# design2.net
KiCad netlist of a schematic drawn in EAGLE
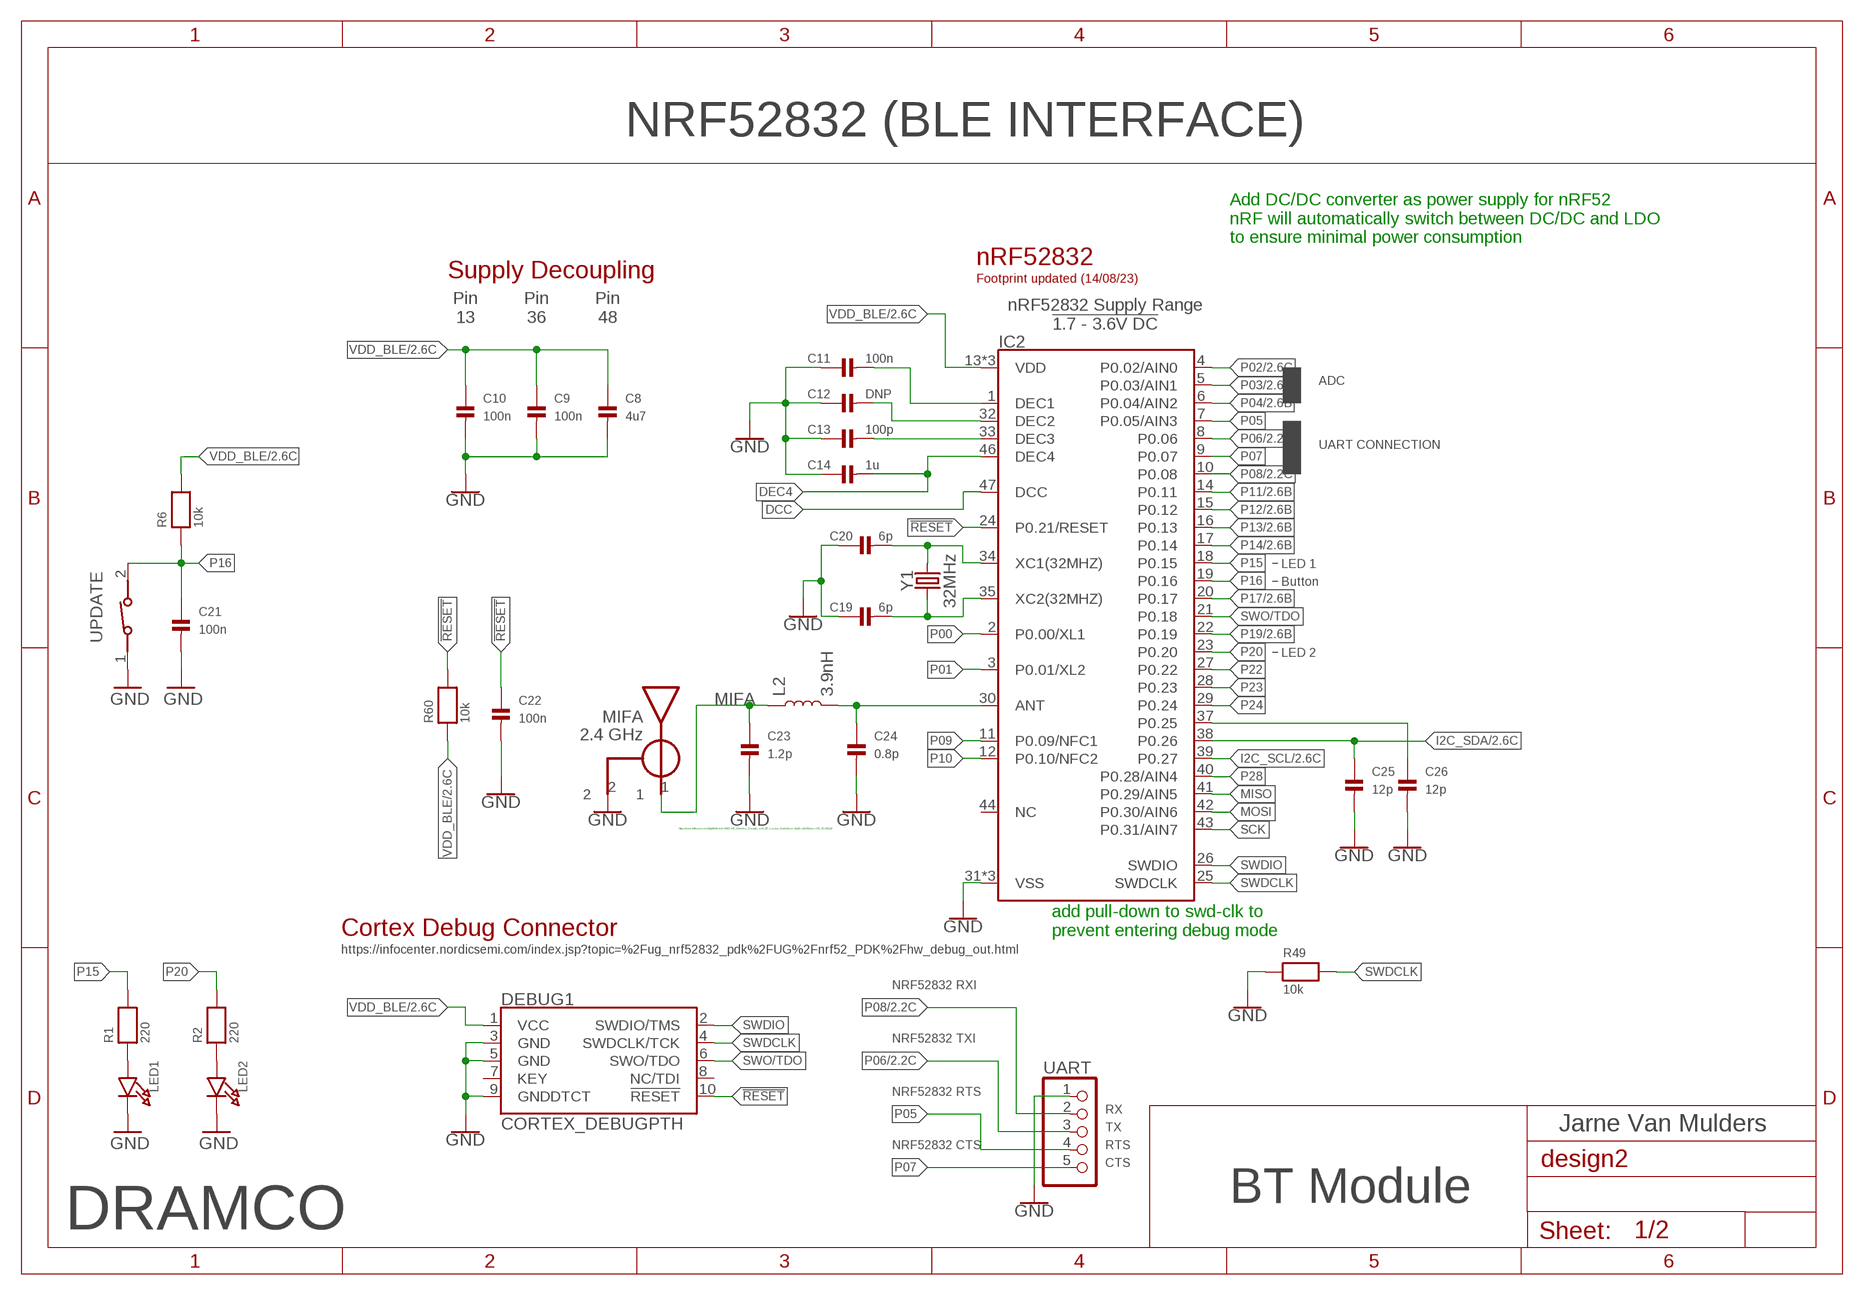
[diagram p0: schematic, sheet 1]
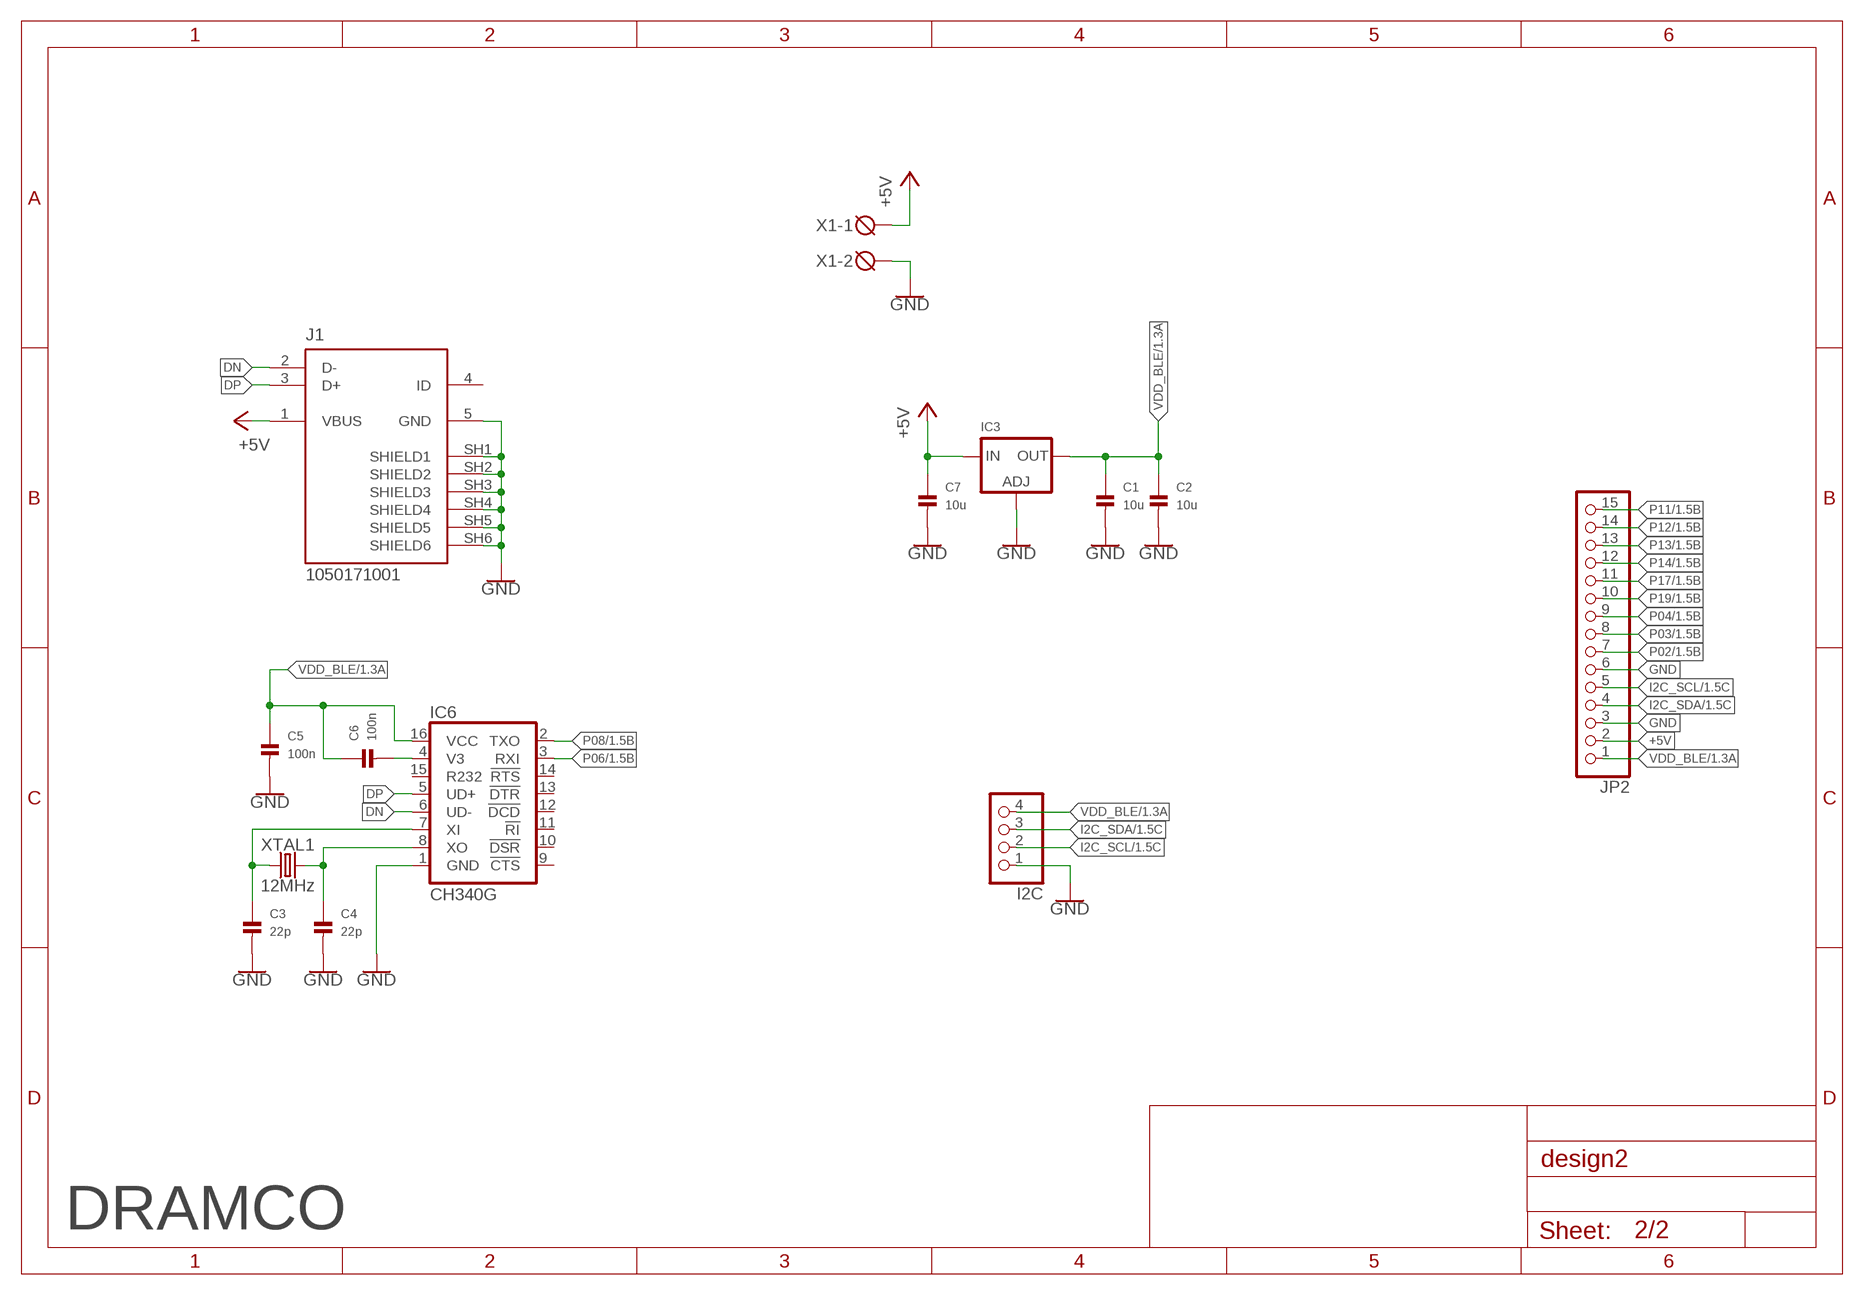
[diagram p1: schematic, sheet 2]

(export (version "E")
  (design (tool "Eeschema 10.0.6"))
  (components
    (comp (ref "C8")
      (value "4u7")
      (footprint "eagle-import:0603")
      (libsource (lib "eagle-import") (part "CAP_CERAMIC0603"))
    )
    (comp (ref "C9")
      (value "100n")
      (footprint "eagle-import:0402")
      (libsource (lib "eagle-import") (part "CAP_CERAMIC0402"))
    )
    (comp (ref "C10")
      (value "100n")
      (footprint "eagle-import:0402")
      (libsource (lib "eagle-import") (part "CAP_CERAMIC0402"))
    )
    (comp (ref "C11")
      (value "100n")
      (footprint "eagle-import:0402")
      (libsource (lib "eagle-import") (part "CAP_CERAMIC0402"))
    )
    (comp (ref "C12")
      (value "DNP")
      (footprint "eagle-import:0402")
      (libsource (lib "eagle-import") (part "CAP_CERAMIC0402"))
    )
    (comp (ref "C13")
      (value "100p")
      (footprint "eagle-import:0402")
      (libsource (lib "eagle-import") (part "CAP_CERAMIC0402"))
    )
    (comp (ref "C14")
      (value "1u")
      (footprint "eagle-import:0402")
      (libsource (lib "eagle-import") (part "CAP_CERAMIC0402"))
    )
    (comp (ref "C19")
      (value "6p")
      (footprint "eagle-import:0402")
      (libsource (lib "eagle-import") (part "CAP_CERAMIC0402"))
    )
    (comp (ref "C20")
      (value "6p")
      (footprint "eagle-import:0402")
      (libsource (lib "eagle-import") (part "CAP_CERAMIC0402"))
    )
    (comp (ref "C21")
      (value "100n")
      (footprint "eagle-import:0402")
      (libsource (lib "eagle-import") (part "CAP_CERAMIC0402"))
    )
    (comp (ref "C22")
      (value "100n")
      (footprint "eagle-import:0402")
      (libsource (lib "eagle-import") (part "CAP_CERAMIC0402"))
    )
    (comp (ref "C23")
      (value "1.2p")
      (footprint "eagle-import:0402")
      (libsource (lib "eagle-import") (part "CAP_CERAMIC0402"))
    )
    (comp (ref "C24")
      (value "0.8p")
      (footprint "eagle-import:0402")
      (libsource (lib "eagle-import") (part "CAP_CERAMIC0402"))
    )
    (comp (ref "C25")
      (value "12p")
      (footprint "eagle-import:0402")
      (libsource (lib "eagle-import") (part "CAP_CERAMIC0402"))
    )
    (comp (ref "C26")
      (value "12p")
      (footprint "eagle-import:0402")
      (libsource (lib "eagle-import") (part "CAP_CERAMIC0402"))
    )
    (comp (ref "DEBUG1")
      (value "CORTEX_DEBUGPTH")
      (footprint "eagle-import:2X5-PTH-1.27MM")
      (libsource (lib "eagle-import") (part "CORTEX_DEBUGPTH"))
    )
    (comp (ref "IC2")
      (value "NRF52832-EXTENDED")
      (footprint "eagle-import:QFN48-6X6MM-EXTENDED")
      (libsource (lib "eagle-import") (part "NRF52832-EXTENDED"))
    )
    (comp (ref "L2")
      (value "3.9nH")
      (footprint "eagle-import:0402")
      (libsource (lib "eagle-import") (part "INDUCTOR-0402-3.9NH"))
    )
    (comp (ref "LED1")
      (value "LED0805")
      (footprint "eagle-import:CHIPLED_0805")
      (libsource (lib "eagle-import") (part "LED0805"))
    )
    (comp (ref "LED2")
      (value "LED0805")
      (footprint "eagle-import:CHIPLED_0805")
      (libsource (lib "eagle-import") (part "LED0805"))
    )
    (comp (ref "R1")
      (value "220")
      (footprint "eagle-import:0603")
      (libsource (lib "eagle-import") (part "RESISTOR0603"))
    )
    (comp (ref "R2")
      (value "220")
      (footprint "eagle-import:0603")
      (libsource (lib "eagle-import") (part "RESISTOR0603"))
    )
    (comp (ref "R6")
      (value "10k")
      (footprint "eagle-import:0402")
      (libsource (lib "eagle-import") (part "RESISTOR0402"))
    )
    (comp (ref "R49")
      (value "10k")
      (footprint "eagle-import:0402")
      (libsource (lib "eagle-import") (part "RESISTOR0402"))
    )
    (comp (ref "R60")
      (value "10k")
      (footprint "eagle-import:0402")
      (libsource (lib "eagle-import") (part "RESISTOR0402"))
    )
    (comp (ref "U$18")
      (value "BLE-ANT")
      (footprint "eagle-import:ANT-2G4")
      (libsource (lib "eagle-import") (part "BLE-ANT"))
    )
    (comp (ref "UART")
      (value "HEADER-1X5ROUND")
      (footprint "eagle-import:1X05_ROUND")
      (libsource (lib "eagle-import") (part "HEADER-1X5ROUND"))
    )
    (comp (ref "UPDATE")
      (value "434111043826")
      (footprint "eagle-import:434111043826")
      (libsource (lib "eagle-import") (part "434111043826"))
    )
    (comp (ref "Y1")
      (value "32MHz")
      (footprint "eagle-import:CRYSTAL-SMD-2.0X1.6MM")
      (libsource (lib "eagle-import") (part "CRYSTAL-32MHZ-SMD-2.0X1.6MM"))
    )
    (comp (ref "C1")
      (value "10u")
      (footprint "eagle-import:0805")
      (libsource (lib "eagle-import") (part "CAP_CERAMIC0805"))
    )
    (comp (ref "C2")
      (value "10u")
      (footprint "eagle-import:0805")
      (libsource (lib "eagle-import") (part "CAP_CERAMIC0805"))
    )
    (comp (ref "C3")
      (value "22p")
      (footprint "eagle-import:0402")
      (libsource (lib "eagle-import") (part "CAP_CERAMIC0402"))
    )
    (comp (ref "C4")
      (value "22p")
      (footprint "eagle-import:0402")
      (libsource (lib "eagle-import") (part "CAP_CERAMIC0402"))
    )
    (comp (ref "C5")
      (value "100n")
      (footprint "eagle-import:0402")
      (libsource (lib "eagle-import") (part "CAP_CERAMIC0402"))
    )
    (comp (ref "C6")
      (value "100n")
      (footprint "eagle-import:0402")
      (libsource (lib "eagle-import") (part "CAP_CERAMIC0402"))
    )
    (comp (ref "C7")
      (value "10u")
      (footprint "eagle-import:0805")
      (libsource (lib "eagle-import") (part "CAP_CERAMIC0805"))
    )
    (comp (ref "I2C")
      (value "HEADER-1X4ROUND")
      (footprint "eagle-import:1X04_ROUND")
      (libsource (lib "eagle-import") (part "HEADER-1X4ROUND"))
    )
    (comp (ref "IC3")
      (value "LM1117SOT223-REFLOW")
      (footprint "eagle-import:SOT223-R")
      (libsource (lib "eagle-import") (part "LM1117SOT223-REFLOW"))
    )
    (comp (ref "IC6")
      (value "CH340G")
      (footprint "eagle-import:SO016")
      (libsource (lib "eagle-import") (part "CH340GSMD"))
    )
    (comp (ref "J1")
      (value "1050171001")
      (footprint "eagle-import:MOLEX_1050171001")
      (fields (field (name "MF") "Molex"))
      (libsource (lib "eagle-import") (part "1050171001"))
    )
    (comp (ref "JP2")
      (value "HEADER-1X15")
      (footprint "eagle-import:1X15_ROUND_70")
      (libsource (lib "eagle-import") (part "HEADER-1X15"))
    )
    (comp (ref "X1")
      (value "DG3XX-02-3.5")
      (footprint "eagle-import:DG350-3.5-02P")
      (libsource (lib "eagle-import") (part "DG3XX-02-3.5"))
    )
    (comp (ref "XTAL1")
      (value "12MHz")
      (footprint "eagle-import:CRYSTAL-SMD-3.2X2.5MM")
      (libsource (lib "eagle-import") (part "CRYSTALSMD-3.2X2.5"))
    )
  )
  (nets
    (net (code "1") (name "+5V") (class "Default")
      (node (ref "C7") (pin "1") (pinfunction "P$1_1") (pintype "passive"))
      (node (ref "IC3") (pin "3") (pinfunction "IN_3") (pintype "input"))
      (node (ref "J1") (pin "1") (pinfunction "VBUS_1") (pintype "power_in"))
      (node (ref "JP2") (pin "2") (pinfunction "2_2") (pintype "passive"))
      (node (ref "X1") (pin "1") (pinfunction "KL_1") (pintype "passive"))
    )
    (net (code "2") (name "DCC") (class "Default")
      (node (ref "IC2") (pin "47") (pinfunction "DCC_47") (pintype "bidirectional"))
    )
    (net (code "3") (name "DEC4") (class "Default")
      (node (ref "C14") (pin "2") (pinfunction "P$2_2") (pintype "passive"))
      (node (ref "IC2") (pin "46") (pinfunction "DEC4_46") (pintype "bidirectional"))
    )
    (net (code "4") (name "DN") (class "Default")
      (node (ref "IC6") (pin "6") (pinfunction "UD-_6") (pintype "bidirectional"))
      (node (ref "J1") (pin "2") (pinfunction "D-_2") (pintype "bidirectional"))
    )
    (net (code "5") (name "DP") (class "Default")
      (node (ref "IC6") (pin "5") (pinfunction "UD+_5") (pintype "bidirectional"))
      (node (ref "J1") (pin "3") (pinfunction "D+_3") (pintype "bidirectional"))
    )
    (net (code "6") (name "GND") (class "Default")
      (node (ref "C1") (pin "2") (pinfunction "P$2_2") (pintype "passive"))
      (node (ref "C10") (pin "2") (pinfunction "P$2_2") (pintype "passive"))
      (node (ref "C11") (pin "1") (pinfunction "P$1_1") (pintype "passive"))
      (node (ref "C12") (pin "1") (pinfunction "P$1_1") (pintype "passive"))
      (node (ref "C13") (pin "1") (pinfunction "P$1_1") (pintype "passive"))
      (node (ref "C14") (pin "1") (pinfunction "P$1_1") (pintype "passive"))
      (node (ref "C19") (pin "1") (pinfunction "P$1_1") (pintype "passive"))
      (node (ref "C2") (pin "2") (pinfunction "P$2_2") (pintype "passive"))
      (node (ref "C20") (pin "1") (pinfunction "P$1_1") (pintype "passive"))
      (node (ref "C21") (pin "2") (pinfunction "P$2_2") (pintype "passive"))
      (node (ref "C22") (pin "2") (pinfunction "P$2_2") (pintype "passive"))
      (node (ref "C23") (pin "2") (pinfunction "P$2_2") (pintype "passive"))
      (node (ref "C24") (pin "2") (pinfunction "P$2_2") (pintype "passive"))
      (node (ref "C25") (pin "2") (pinfunction "P$2_2") (pintype "passive"))
      (node (ref "C26") (pin "2") (pinfunction "P$2_2") (pintype "passive"))
      (node (ref "C3") (pin "2") (pinfunction "P$2_2") (pintype "passive"))
      (node (ref "C4") (pin "2") (pinfunction "P$2_2") (pintype "passive"))
      (node (ref "C5") (pin "2") (pinfunction "P$2_2") (pintype "passive"))
      (node (ref "C7") (pin "2") (pinfunction "P$2_2") (pintype "passive"))
      (node (ref "C8") (pin "2") (pinfunction "P$2_2") (pintype "passive"))
      (node (ref "C9") (pin "2") (pinfunction "P$2_2") (pintype "passive"))
      (node (ref "DEBUG1") (pin "3") (pinfunction "GND_3") (pintype "bidirectional"))
      (node (ref "DEBUG1") (pin "5") (pinfunction "GND_5") (pintype "bidirectional"))
      (node (ref "DEBUG1") (pin "9") (pinfunction "GNDDTCT_9") (pintype "bidirectional"))
      (node (ref "I2C") (pin "1") (pinfunction "1_1") (pintype "passive"))
      (node (ref "IC2") (pin "31") (pinfunction "VSS_31") (pintype "bidirectional"))
      (node (ref "IC2") (pin "45") (pinfunction "VSS_45") (pintype "bidirectional"))
      (node (ref "IC2") (pin "EP") (pinfunction "VSS_EP") (pintype "bidirectional"))
      (node (ref "IC3") (pin "1") (pinfunction "ADJ_1") (pintype "input"))
      (node (ref "IC6") (pin "1") (pinfunction "GND_1") (pintype "bidirectional"))
      (node (ref "J1") (pin "5") (pinfunction "GND_5") (pintype "power_in"))
      (node (ref "J1") (pin "SH1") (pinfunction "SHIELD1_SH1") (pintype "passive"))
      (node (ref "J1") (pin "SH2") (pinfunction "SHIELD2_SH2") (pintype "passive"))
      (node (ref "J1") (pin "SH3") (pinfunction "SHIELD3_SH3") (pintype "passive"))
      (node (ref "J1") (pin "SH4") (pinfunction "SHIELD4_SH4") (pintype "passive"))
      (node (ref "J1") (pin "SH5") (pinfunction "SHIELD5_SH5") (pintype "passive"))
      (node (ref "J1") (pin "SH6") (pinfunction "SHIELD6_SH6") (pintype "passive"))
      (node (ref "JP2") (pin "3") (pinfunction "3_3") (pintype "passive"))
      (node (ref "JP2") (pin "6") (pinfunction "6_6") (pintype "passive"))
      (node (ref "LED1") (pin "C") (pinfunction "C_C") (pintype "passive"))
      (node (ref "LED2") (pin "C") (pinfunction "C_C") (pintype "passive"))
      (node (ref "R49") (pin "1") (pinfunction "1_1") (pintype "passive"))
      (node (ref "U$18") (pin "2") (pinfunction "2_2") (pintype "bidirectional"))
      (node (ref "UART") (pin "1") (pinfunction "1_1") (pintype "passive"))
      (node (ref "UPDATE") (pin "1") (pinfunction "1_1") (pintype "passive"))
      (node (ref "X1") (pin "2") (pinfunction "KL_2") (pintype "passive"))
    )
    (net (code "7") (name "I2C_SCL") (class "Default")
      (node (ref "I2C") (pin "2") (pinfunction "2_2") (pintype "passive"))
      (node (ref "IC2") (pin "39") (pinfunction "P0.27_39") (pintype "bidirectional"))
      (node (ref "JP2") (pin "5") (pinfunction "5_5") (pintype "passive"))
    )
    (net (code "8") (name "I2C_SDA") (class "Default")
      (node (ref "C25") (pin "1") (pinfunction "P$1_1") (pintype "passive"))
      (node (ref "I2C") (pin "3") (pinfunction "3_3") (pintype "passive"))
      (node (ref "IC2") (pin "38") (pinfunction "P0.26_38") (pintype "bidirectional"))
      (node (ref "JP2") (pin "4") (pinfunction "4_4") (pintype "passive"))
    )
    (net (code "9") (name "MIFA") (class "Default")
      (node (ref "C23") (pin "1") (pinfunction "P$1_1") (pintype "passive"))
      (node (ref "L2") (pin "1") (pinfunction "1_1") (pintype "passive"))
      (node (ref "U$18") (pin "1") (pinfunction "1_1") (pintype "bidirectional"))
    )
    (net (code "10") (name "MISO") (class "Default")
      (node (ref "IC2") (pin "41") (pinfunction "P0.29/AIN5_41") (pintype "bidirectional"))
    )
    (net (code "11") (name "MOSI") (class "Default")
      (node (ref "IC2") (pin "42") (pinfunction "P0.30/AIN6_42") (pintype "bidirectional"))
    )
    (net (code "12") (name "Net-(C3-P$1)") (class "Default")
      (node (ref "C3") (pin "1") (pinfunction "P$1_1") (pintype "passive"))
      (node (ref "IC6") (pin "7") (pinfunction "XI_7") (pintype "bidirectional"))
      (node (ref "XTAL1") (pin "1") (pinfunction "1_1") (pintype "passive"))
    )
    (net (code "13") (name "Net-(C4-P$1)") (class "Default")
      (node (ref "C4") (pin "1") (pinfunction "P$1_1") (pintype "passive"))
      (node (ref "IC6") (pin "8") (pinfunction "XO_8") (pintype "bidirectional"))
      (node (ref "XTAL1") (pin "3") (pinfunction "2_3") (pintype "passive"))
    )
    (net (code "14") (name "Net-(C6-P$2)") (class "Default")
      (node (ref "C6") (pin "2") (pinfunction "P$2_2") (pintype "passive"))
      (node (ref "IC6") (pin "4") (pinfunction "V3_4") (pintype "bidirectional"))
    )
    (net (code "15") (name "Net-(C11-P$2)") (class "Default")
      (node (ref "C11") (pin "2") (pinfunction "P$2_2") (pintype "passive"))
      (node (ref "IC2") (pin "1") (pinfunction "DEC1_1") (pintype "bidirectional"))
    )
    (net (code "16") (name "Net-(C12-P$2)") (class "Default")
      (node (ref "C12") (pin "2") (pinfunction "P$2_2") (pintype "passive"))
      (node (ref "IC2") (pin "32") (pinfunction "DEC2_32") (pintype "bidirectional"))
    )
    (net (code "17") (name "Net-(C13-P$2)") (class "Default")
      (node (ref "C13") (pin "2") (pinfunction "P$2_2") (pintype "passive"))
      (node (ref "IC2") (pin "33") (pinfunction "DEC3_33") (pintype "bidirectional"))
    )
    (net (code "18") (name "Net-(C19-P$2)") (class "Default")
      (node (ref "C19") (pin "2") (pinfunction "P$2_2") (pintype "passive"))
      (node (ref "IC2") (pin "35") (pinfunction "XC2(32MHZ)_35") (pintype "bidirectional"))
      (node (ref "Y1") (pin "1") (pinfunction "1_1") (pintype "passive"))
    )
    (net (code "19") (name "Net-(C20-P$2)") (class "Default")
      (node (ref "C20") (pin "2") (pinfunction "P$2_2") (pintype "passive"))
      (node (ref "IC2") (pin "34") (pinfunction "XC1(32MHZ)_34") (pintype "bidirectional"))
      (node (ref "Y1") (pin "3") (pinfunction "2_3") (pintype "passive"))
    )
    (net (code "20") (name "Net-(C24-P$1)") (class "Default")
      (node (ref "C24") (pin "1") (pinfunction "P$1_1") (pintype "passive"))
      (node (ref "IC2") (pin "30") (pinfunction "ANT_30") (pintype "bidirectional"))
      (node (ref "L2") (pin "2") (pinfunction "2_2") (pintype "passive"))
    )
    (net (code "21") (name "Net-(C26-P$1)") (class "Default")
      (node (ref "C26") (pin "1") (pinfunction "P$1_1") (pintype "passive"))
      (node (ref "IC2") (pin "37") (pinfunction "P0.25_37") (pintype "bidirectional"))
    )
    (net (code "22") (name "Net-(LED1-PadA)") (class "Default")
      (node (ref "LED1") (pin "A") (pinfunction "A_A") (pintype "passive"))
      (node (ref "R1") (pin "1") (pinfunction "1_1") (pintype "passive"))
    )
    (net (code "23") (name "Net-(LED2-PadA)") (class "Default")
      (node (ref "LED2") (pin "A") (pinfunction "A_A") (pintype "passive"))
      (node (ref "R2") (pin "1") (pinfunction "1_1") (pintype "passive"))
    )
    (net (code "24") (name "P00") (class "Default")
      (node (ref "IC2") (pin "2") (pinfunction "P0.00/XL1_2") (pintype "bidirectional"))
    )
    (net (code "25") (name "P01") (class "Default")
      (node (ref "IC2") (pin "3") (pinfunction "P0.01/XL2_3") (pintype "bidirectional"))
    )
    (net (code "26") (name "P02") (class "Default")
      (node (ref "IC2") (pin "4") (pinfunction "P0.02/AIN0_4") (pintype "bidirectional"))
      (node (ref "JP2") (pin "7") (pinfunction "7_7") (pintype "passive"))
    )
    (net (code "27") (name "P03") (class "Default")
      (node (ref "IC2") (pin "5") (pinfunction "P0.03/AIN1_5") (pintype "bidirectional"))
      (node (ref "JP2") (pin "8") (pinfunction "8_8") (pintype "passive"))
    )
    (net (code "28") (name "P04") (class "Default")
      (node (ref "IC2") (pin "6") (pinfunction "P0.04/AIN2_6") (pintype "bidirectional"))
      (node (ref "JP2") (pin "9") (pinfunction "9_9") (pintype "passive"))
    )
    (net (code "29") (name "P05") (class "Default")
      (node (ref "IC2") (pin "7") (pinfunction "P0.05/AIN3_7") (pintype "bidirectional"))
      (node (ref "UART") (pin "4") (pinfunction "4_4") (pintype "passive"))
    )
    (net (code "30") (name "P06") (class "Default")
      (node (ref "IC2") (pin "8") (pinfunction "P0.06_8") (pintype "bidirectional"))
      (node (ref "IC6") (pin "3") (pinfunction "RXI_3") (pintype "bidirectional"))
      (node (ref "UART") (pin "3") (pinfunction "3_3") (pintype "passive"))
    )
    (net (code "31") (name "P07") (class "Default")
      (node (ref "IC2") (pin "9") (pinfunction "P0.07_9") (pintype "bidirectional"))
      (node (ref "UART") (pin "5") (pinfunction "5_5") (pintype "passive"))
    )
    (net (code "32") (name "P08") (class "Default")
      (node (ref "IC2") (pin "10") (pinfunction "P0.08_10") (pintype "bidirectional"))
      (node (ref "IC6") (pin "2") (pinfunction "TXO_2") (pintype "bidirectional"))
      (node (ref "UART") (pin "2") (pinfunction "2_2") (pintype "passive"))
    )
    (net (code "33") (name "P09") (class "Default")
      (node (ref "IC2") (pin "11") (pinfunction "P0.09/NFC1_11") (pintype "bidirectional"))
    )
    (net (code "34") (name "P10") (class "Default")
      (node (ref "IC2") (pin "12") (pinfunction "P0.10/NFC2_12") (pintype "bidirectional"))
    )
    (net (code "35") (name "P11") (class "Default")
      (node (ref "IC2") (pin "14") (pinfunction "P0.11_14") (pintype "bidirectional"))
      (node (ref "JP2") (pin "15") (pinfunction "15_15") (pintype "passive"))
    )
    (net (code "36") (name "P12") (class "Default")
      (node (ref "IC2") (pin "15") (pinfunction "P0.12_15") (pintype "bidirectional"))
      (node (ref "JP2") (pin "14") (pinfunction "14_14") (pintype "passive"))
    )
    (net (code "37") (name "P13") (class "Default")
      (node (ref "IC2") (pin "16") (pinfunction "P0.13_16") (pintype "bidirectional"))
      (node (ref "JP2") (pin "13") (pinfunction "13_13") (pintype "passive"))
    )
    (net (code "38") (name "P14") (class "Default")
      (node (ref "IC2") (pin "17") (pinfunction "P0.14_17") (pintype "bidirectional"))
      (node (ref "JP2") (pin "12") (pinfunction "12_12") (pintype "passive"))
    )
    (net (code "39") (name "P15") (class "Default")
      (node (ref "IC2") (pin "18") (pinfunction "P0.15_18") (pintype "bidirectional"))
      (node (ref "R1") (pin "2") (pinfunction "2_2") (pintype "passive"))
    )
    (net (code "40") (name "P16") (class "Default")
      (node (ref "C21") (pin "1") (pinfunction "P$1_1") (pintype "passive"))
      (node (ref "IC2") (pin "19") (pinfunction "P0.16_19") (pintype "bidirectional"))
      (node (ref "R6") (pin "1") (pinfunction "1_1") (pintype "passive"))
      (node (ref "UPDATE") (pin "2") (pinfunction "2_2") (pintype "passive"))
    )
    (net (code "41") (name "P17") (class "Default")
      (node (ref "IC2") (pin "20") (pinfunction "P0.17_20") (pintype "bidirectional"))
      (node (ref "JP2") (pin "11") (pinfunction "11_11") (pintype "passive"))
    )
    (net (code "42") (name "P19") (class "Default")
      (node (ref "IC2") (pin "22") (pinfunction "P0.19_22") (pintype "bidirectional"))
      (node (ref "JP2") (pin "10") (pinfunction "10_10") (pintype "passive"))
    )
    (net (code "43") (name "P20") (class "Default")
      (node (ref "IC2") (pin "23") (pinfunction "P0.20_23") (pintype "bidirectional"))
      (node (ref "R2") (pin "2") (pinfunction "2_2") (pintype "passive"))
    )
    (net (code "44") (name "P22") (class "Default")
      (node (ref "IC2") (pin "27") (pinfunction "P0.22_27") (pintype "bidirectional"))
    )
    (net (code "45") (name "P23") (class "Default")
      (node (ref "IC2") (pin "28") (pinfunction "P0.23_28") (pintype "bidirectional"))
    )
    (net (code "46") (name "P24") (class "Default")
      (node (ref "IC2") (pin "29") (pinfunction "P0.24_29") (pintype "bidirectional"))
    )
    (net (code "47") (name "P28") (class "Default")
      (node (ref "IC2") (pin "40") (pinfunction "P0.28/AIN4_40") (pintype "bidirectional"))
    )
    (net (code "48") (name "SCK") (class "Default")
      (node (ref "IC2") (pin "43") (pinfunction "P0.31/AIN7_43") (pintype "bidirectional"))
    )
    (net (code "49") (name "SWDCLK") (class "Default")
      (node (ref "DEBUG1") (pin "4") (pinfunction "SWDCLK/TCK_4") (pintype "bidirectional"))
      (node (ref "IC2") (pin "25") (pinfunction "SWDCLK_25") (pintype "bidirectional"))
      (node (ref "R49") (pin "2") (pinfunction "2_2") (pintype "passive"))
    )
    (net (code "50") (name "SWDIO") (class "Default")
      (node (ref "DEBUG1") (pin "2") (pinfunction "SWDIO/TMS_2") (pintype "bidirectional"))
      (node (ref "IC2") (pin "26") (pinfunction "SWDIO_26") (pintype "bidirectional"))
    )
    (net (code "51") (name "SWO{slash}TDO") (class "Default")
      (node (ref "DEBUG1") (pin "6") (pinfunction "SWO/TDO_6") (pintype "bidirectional"))
      (node (ref "IC2") (pin "21") (pinfunction "P0.18_21") (pintype "bidirectional"))
    )
    (net (code "52") (name "VDD_BLE") (class "Default")
      (node (ref "C1") (pin "1") (pinfunction "P$1_1") (pintype "passive"))
      (node (ref "C10") (pin "1") (pinfunction "P$1_1") (pintype "passive"))
      (node (ref "C2") (pin "1") (pinfunction "P$1_1") (pintype "passive"))
      (node (ref "C5") (pin "1") (pinfunction "P$1_1") (pintype "passive"))
      (node (ref "C6") (pin "1") (pinfunction "P$1_1") (pintype "passive"))
      (node (ref "C8") (pin "1") (pinfunction "P$1_1") (pintype "passive"))
      (node (ref "C9") (pin "1") (pinfunction "P$1_1") (pintype "passive"))
      (node (ref "DEBUG1") (pin "1") (pinfunction "VCC_1") (pintype "bidirectional"))
      (node (ref "I2C") (pin "4") (pinfunction "4_4") (pintype "passive"))
      (node (ref "IC2") (pin "13") (pinfunction "VDD_13") (pintype "bidirectional"))
      (node (ref "IC2") (pin "36") (pinfunction "VDD_36") (pintype "bidirectional"))
      (node (ref "IC2") (pin "48") (pinfunction "VDD_48") (pintype "bidirectional"))
      (node (ref "IC3") (pin "2") (pinfunction "OUT_2") (pintype "passive"))
      (node (ref "IC6") (pin "16") (pinfunction "VCC_16") (pintype "bidirectional"))
      (node (ref "JP2") (pin "1") (pinfunction "1_1") (pintype "passive"))
      (node (ref "R6") (pin "2") (pinfunction "2_2") (pintype "passive"))
      (node (ref "R60") (pin "1") (pinfunction "1_1") (pintype "passive"))
    )
    (net (code "53") (name "unconnected-(DEBUG1-KEY-Pad7)") (class "Default")
      (node (ref "DEBUG1") (pin "7") (pinfunction "KEY_7") (pintype "bidirectional"))
    )
    (net (code "54") (name "unconnected-(DEBUG1-NC{slash}TDI-Pad8)") (class "Default")
      (node (ref "DEBUG1") (pin "8") (pinfunction "NC/TDI_8") (pintype "bidirectional"))
    )
    (net (code "55") (name "unconnected-(IC2-NC-Pad44)") (class "Default")
      (node (ref "IC2") (pin "44") (pinfunction "NC_44") (pintype "bidirectional"))
    )
    (net (code "56") (name "unconnected-(IC6-R232-Pad15)") (class "Default")
      (node (ref "IC6") (pin "15") (pinfunction "R232_15") (pintype "bidirectional"))
    )
    (net (code "57") (name "unconnected-(IC6-~{CTS}-Pad9)") (class "Default")
      (node (ref "IC6") (pin "9") (pinfunction "~{CTS}_9") (pintype "bidirectional"))
    )
    (net (code "58") (name "unconnected-(IC6-~{DCD}-Pad12)") (class "Default")
      (node (ref "IC6") (pin "12") (pinfunction "~{DCD}_12") (pintype "bidirectional"))
    )
    (net (code "59") (name "unconnected-(IC6-~{DSR}-Pad10)") (class "Default")
      (node (ref "IC6") (pin "10") (pinfunction "~{DSR}_10") (pintype "bidirectional"))
    )
    (net (code "60") (name "unconnected-(IC6-~{DTR}-Pad13)") (class "Default")
      (node (ref "IC6") (pin "13") (pinfunction "~{DTR}_13") (pintype "bidirectional"))
    )
    (net (code "61") (name "unconnected-(IC6-~{RI}-Pad11)") (class "Default")
      (node (ref "IC6") (pin "11") (pinfunction "~{RI}_11") (pintype "bidirectional"))
    )
    (net (code "62") (name "unconnected-(IC6-~{RTS}-Pad14)") (class "Default")
      (node (ref "IC6") (pin "14") (pinfunction "~{RTS}_14") (pintype "bidirectional"))
    )
    (net (code "63") (name "unconnected-(J1-ID-Pad4)") (class "Default")
      (node (ref "J1") (pin "4") (pinfunction "ID_4") (pintype "bidirectional"))
    )
    (net (code "64") (name "~{RESET}") (class "Default")
      (node (ref "C22") (pin "1") (pinfunction "P$1_1") (pintype "passive"))
      (node (ref "DEBUG1") (pin "10") (pinfunction "~{RESET}_10") (pintype "bidirectional"))
      (node (ref "IC2") (pin "24") (pinfunction "P0.21/RESET_24") (pintype "bidirectional"))
      (node (ref "R60") (pin "2") (pinfunction "2_2") (pintype "passive"))
    )
  )
)
